# SCH___2023-02-11.net
KiCad netlist of a schematic drawn in EasyEDA
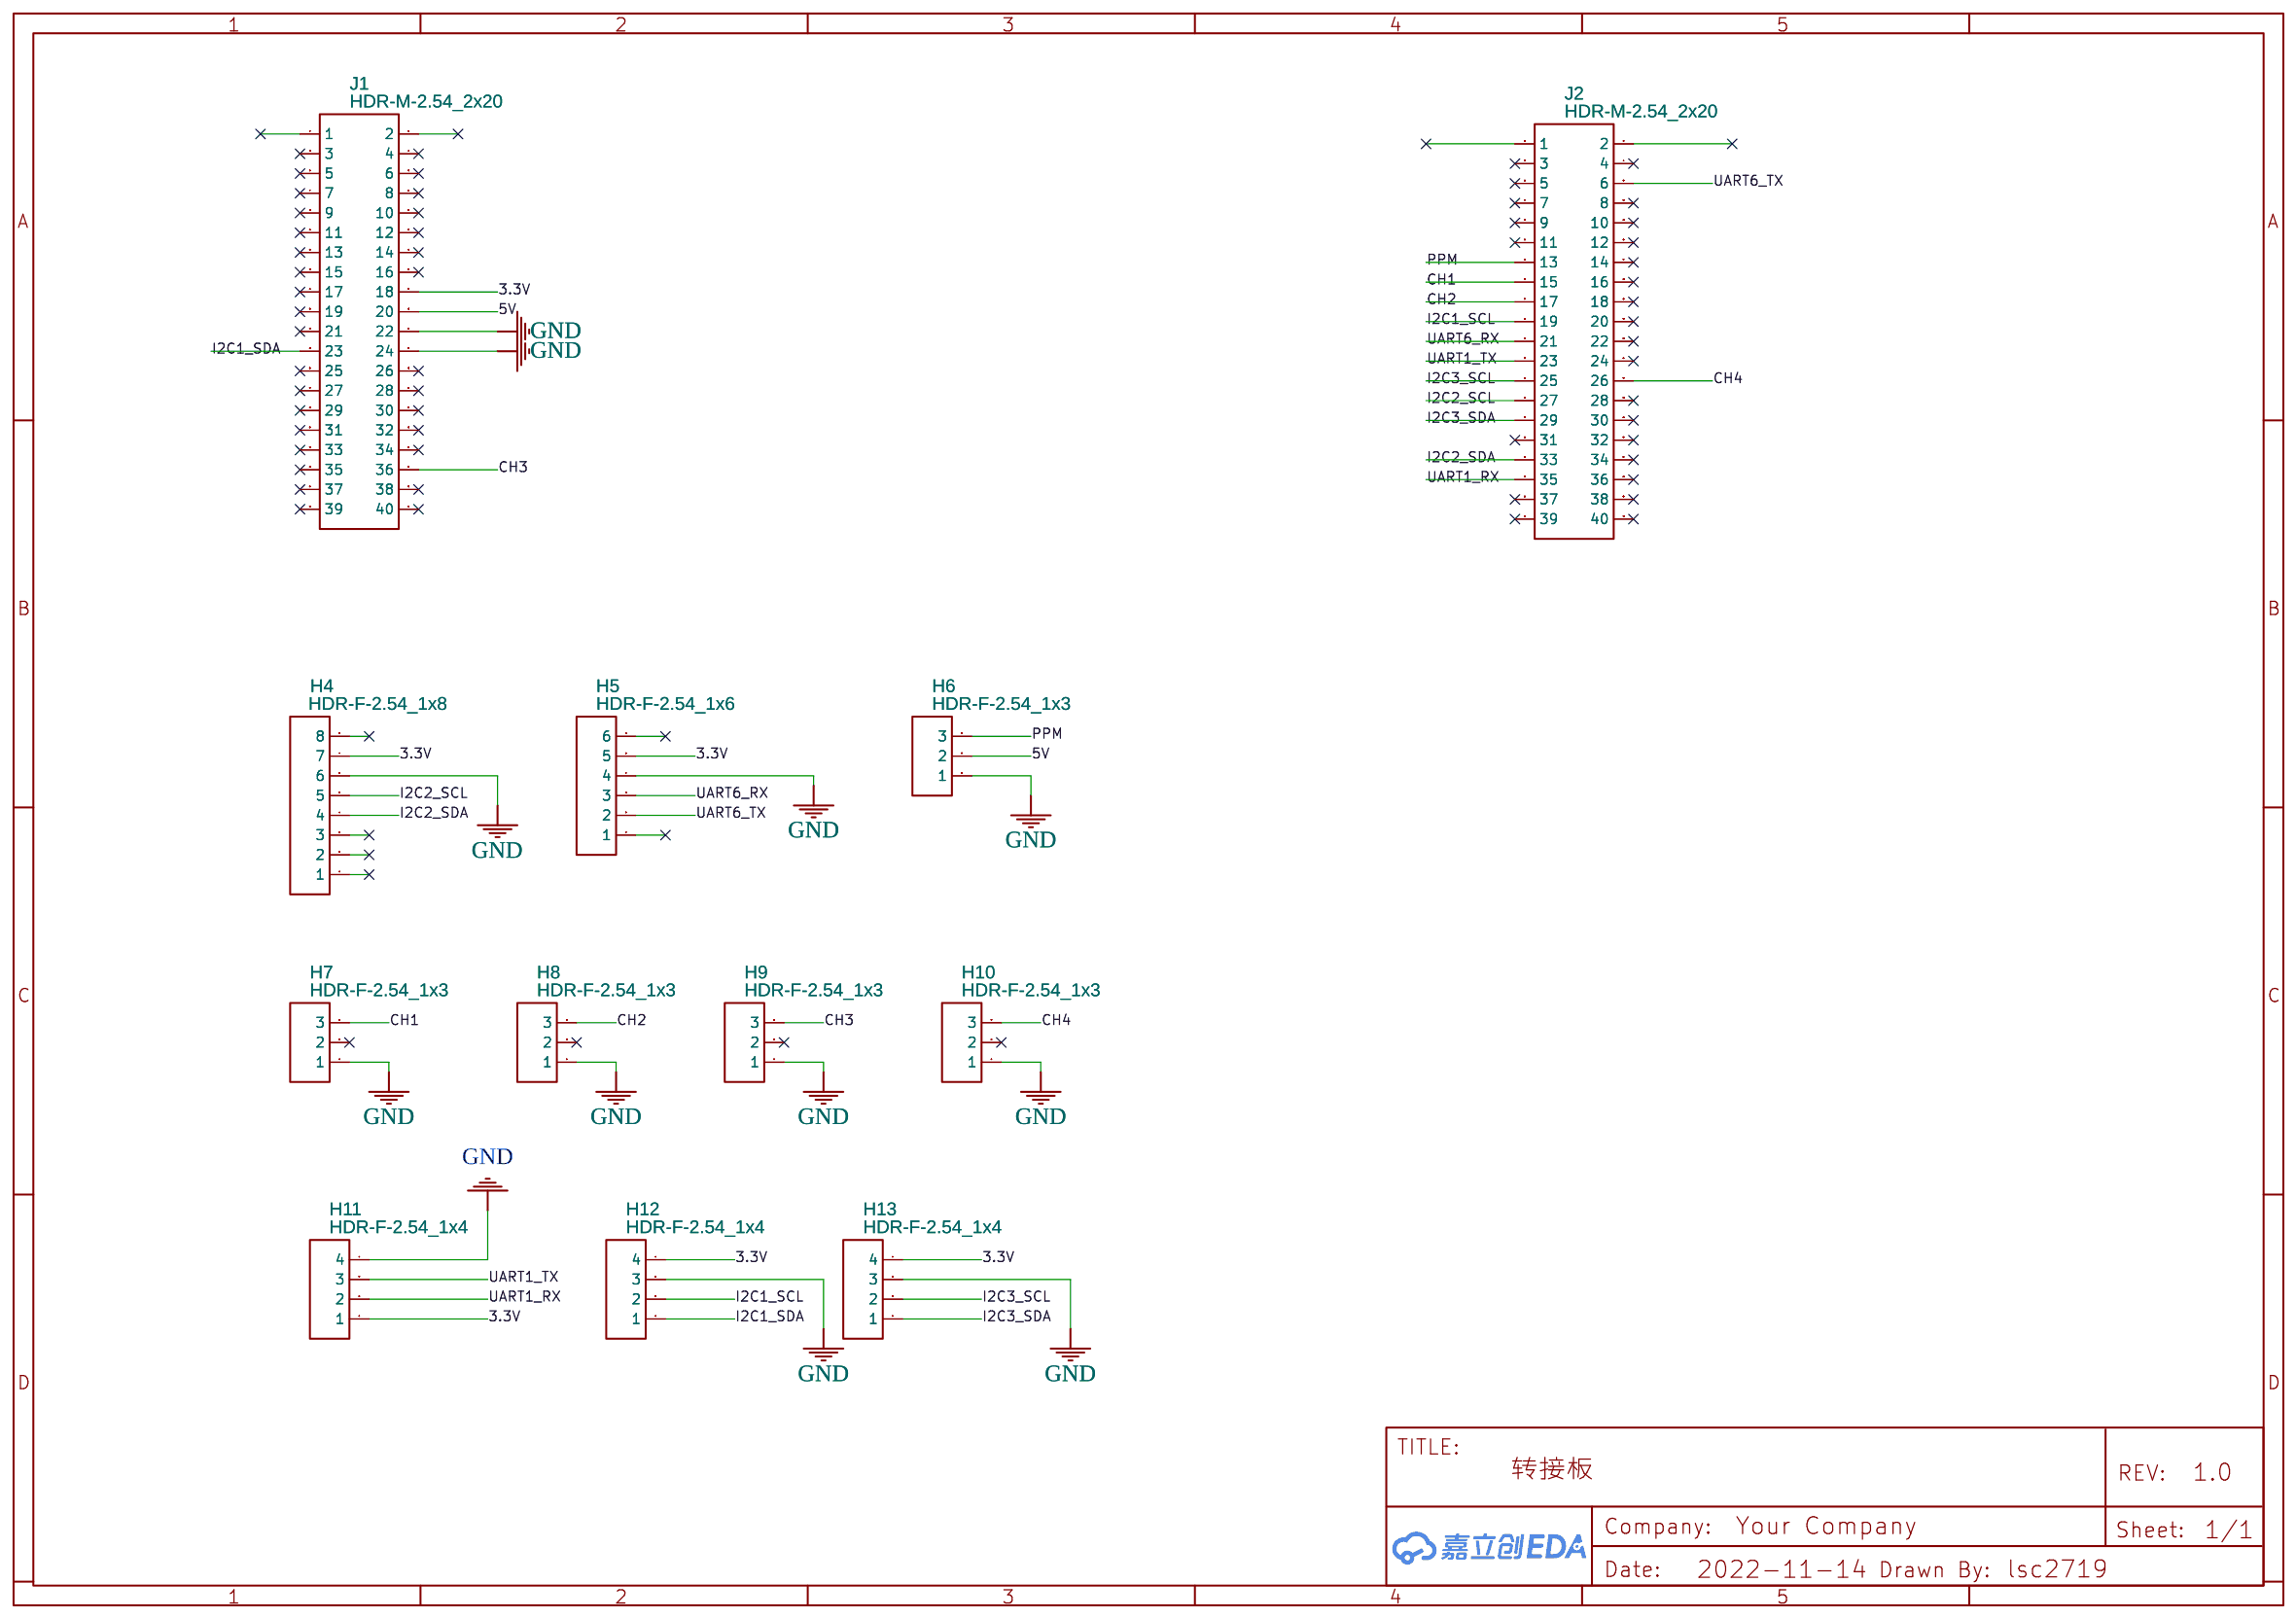
[diagram p0: schematic sheet]

(export (version "E")
  (design (tool "Eeschema 10.0.6"))
  (components
    (comp (ref "H4")
      (value "HDR-F-2.54_1x8")
      (fields (field (name "BOM_Supplier Part") "C225505"))
      (libsource (lib "") (part "HDR-F-2.54_1x8"))
    )
    (comp (ref "H5")
      (value "HDR-F-2.54_1x6")
      (fields (field (name "BOM_Supplier Part") "C40877"))
      (libsource (lib "") (part "HDR-F-2.54_1x6"))
    )
    (comp (ref "H6")
      (value "HDR-F-2.54_1x3")
      (fields (field (name "BOM_Supplier Part") "C146690"))
      (libsource (lib "") (part "HDR-F-2.54_1x3"))
    )
    (comp (ref "H7")
      (value "HDR-F-2.54_1x3")
      (fields (field (name "BOM_Supplier Part") "C146690"))
      (libsource (lib "") (part "HDR-F-2.54_1x3"))
    )
    (comp (ref "H8")
      (value "HDR-F-2.54_1x3")
      (fields (field (name "BOM_Supplier Part") "C146690"))
      (libsource (lib "") (part "HDR-F-2.54_1x3"))
    )
    (comp (ref "H9")
      (value "HDR-F-2.54_1x3")
      (fields (field (name "BOM_Supplier Part") "C146690"))
      (libsource (lib "") (part "HDR-F-2.54_1x3"))
    )
    (comp (ref "H10")
      (value "HDR-F-2.54_1x3")
      (fields (field (name "BOM_Supplier Part") "C146690"))
      (libsource (lib "") (part "HDR-F-2.54_1x3"))
    )
    (comp (ref "H11")
      (value "HDR-F-2.54_1x4")
      (fields (field (name "BOM_Supplier Part") "C225501"))
      (libsource (lib "") (part "HDR-F-2.54_1x4"))
    )
    (comp (ref "H12")
      (value "HDR-F-2.54_1x4")
      (fields (field (name "BOM_Supplier Part") "C225501"))
      (libsource (lib "") (part "HDR-F-2.54_1x4"))
    )
    (comp (ref "H13")
      (value "HDR-F-2.54_1x4")
      (fields (field (name "BOM_Supplier Part") "C225501"))
      (libsource (lib "") (part "HDR-F-2.54_1x4"))
    )
    (comp (ref "J1")
      (value "HDR-M-2.54_2x20")
      (fields (field (name "BOM_Supplier Part") "C50980"))
      (libsource (lib "") (part "HDR-M-2.54_2x20"))
    )
    (comp (ref "J2")
      (value "HDR-M-2.54_2x20")
      (fields (field (name "BOM_Supplier Part") "C50980"))
      (libsource (lib "") (part "HDR-M-2.54_2x20"))
    )
  )
  (nets
    (net (code "1") (name "/3.3V") (class "Default")
      (node (ref "H11") (pin "1") (pinfunction "1_1") (pintype "unspecified"))
      (node (ref "H12") (pin "4") (pinfunction "4_4") (pintype "unspecified"))
      (node (ref "H13") (pin "4") (pinfunction "4_4") (pintype "unspecified"))
      (node (ref "H4") (pin "7") (pinfunction "7_7") (pintype "unspecified"))
      (node (ref "H5") (pin "5") (pinfunction "5_5") (pintype "input"))
      (node (ref "J1") (pin "18") (pinfunction "18_18") (pintype "input"))
    )
    (net (code "2") (name "/5V") (class "Default")
      (node (ref "H6") (pin "2") (pinfunction "2_2") (pintype "input"))
      (node (ref "J1") (pin "20") (pinfunction "20_20") (pintype "input"))
    )
    (net (code "3") (name "/CH1") (class "Default")
      (node (ref "H7") (pin "3") (pinfunction "3_3") (pintype "input"))
      (node (ref "J2") (pin "15") (pinfunction "15_15") (pintype "input"))
    )
    (net (code "4") (name "/CH2") (class "Default")
      (node (ref "H8") (pin "3") (pinfunction "3_3") (pintype "input"))
      (node (ref "J2") (pin "17") (pinfunction "17_17") (pintype "input"))
    )
    (net (code "5") (name "/CH3") (class "Default")
      (node (ref "H9") (pin "3") (pinfunction "3_3") (pintype "input"))
      (node (ref "J1") (pin "36") (pinfunction "36_36") (pintype "input"))
    )
    (net (code "6") (name "/CH4") (class "Default")
      (node (ref "H10") (pin "3") (pinfunction "3_3") (pintype "input"))
      (node (ref "J2") (pin "26") (pinfunction "26_26") (pintype "input"))
    )
    (net (code "7") (name "/I2C1_SCL") (class "Default")
      (node (ref "H12") (pin "2") (pinfunction "2_2") (pintype "unspecified"))
      (node (ref "J2") (pin "19") (pinfunction "19_19") (pintype "input"))
    )
    (net (code "8") (name "/I2C1_SDA") (class "Default")
      (node (ref "H12") (pin "1") (pinfunction "1_1") (pintype "unspecified"))
      (node (ref "J1") (pin "23") (pinfunction "23_23") (pintype "input"))
    )
    (net (code "9") (name "/I2C2_SCL") (class "Default")
      (node (ref "H4") (pin "5") (pinfunction "5_5") (pintype "unspecified"))
      (node (ref "J2") (pin "27") (pinfunction "27_27") (pintype "input"))
    )
    (net (code "10") (name "/I2C2_SDA") (class "Default")
      (node (ref "H4") (pin "4") (pinfunction "4_4") (pintype "unspecified"))
      (node (ref "J2") (pin "33") (pinfunction "33_33") (pintype "input"))
    )
    (net (code "11") (name "/I2C3_SCL") (class "Default")
      (node (ref "H13") (pin "2") (pinfunction "2_2") (pintype "unspecified"))
      (node (ref "J2") (pin "25") (pinfunction "25_25") (pintype "input"))
    )
    (net (code "12") (name "/I2C3_SDA") (class "Default")
      (node (ref "H13") (pin "1") (pinfunction "1_1") (pintype "unspecified"))
      (node (ref "J2") (pin "29") (pinfunction "29_29") (pintype "input"))
    )
    (net (code "13") (name "/PPM") (class "Default")
      (node (ref "H6") (pin "3") (pinfunction "3_3") (pintype "input"))
      (node (ref "J2") (pin "13") (pinfunction "13_13") (pintype "input"))
    )
    (net (code "14") (name "/UART1_RX") (class "Default")
      (node (ref "H11") (pin "2") (pinfunction "2_2") (pintype "unspecified"))
      (node (ref "J2") (pin "35") (pinfunction "35_35") (pintype "input"))
    )
    (net (code "15") (name "/UART1_TX") (class "Default")
      (node (ref "H11") (pin "3") (pinfunction "3_3") (pintype "unspecified"))
      (node (ref "J2") (pin "23") (pinfunction "23_23") (pintype "input"))
    )
    (net (code "16") (name "/UART6_RX") (class "Default")
      (node (ref "H5") (pin "3") (pinfunction "3_3") (pintype "input"))
      (node (ref "J2") (pin "21") (pinfunction "21_21") (pintype "input"))
    )
    (net (code "17") (name "/UART6_TX") (class "Default")
      (node (ref "H5") (pin "2") (pinfunction "2_2") (pintype "input"))
      (node (ref "J2") (pin "6") (pinfunction "6_6") (pintype "input"))
    )
    (net (code "18") (name "GND") (class "Default")
      (node (ref "H10") (pin "1") (pinfunction "1_1") (pintype "input"))
      (node (ref "H11") (pin "4") (pinfunction "4_4") (pintype "unspecified"))
      (node (ref "H12") (pin "3") (pinfunction "3_3") (pintype "unspecified"))
      (node (ref "H13") (pin "3") (pinfunction "3_3") (pintype "unspecified"))
      (node (ref "H4") (pin "6") (pinfunction "6_6") (pintype "unspecified"))
      (node (ref "H5") (pin "4") (pinfunction "4_4") (pintype "input"))
      (node (ref "H6") (pin "1") (pinfunction "1_1") (pintype "input"))
      (node (ref "H7") (pin "1") (pinfunction "1_1") (pintype "input"))
      (node (ref "H8") (pin "1") (pinfunction "1_1") (pintype "input"))
      (node (ref "H9") (pin "1") (pinfunction "1_1") (pintype "input"))
      (node (ref "J1") (pin "22") (pinfunction "22_22") (pintype "input"))
      (node (ref "J1") (pin "24") (pinfunction "24_24") (pintype "input"))
    )
    (net (code "19") (name "unconnected-(H4-Pad1)") (class "Default")
      (node (ref "H4") (pin "1") (pinfunction "1_1") (pintype "unspecified+no_connect"))
    )
    (net (code "20") (name "unconnected-(H4-Pad2)") (class "Default")
      (node (ref "H4") (pin "2") (pinfunction "2_2") (pintype "unspecified+no_connect"))
    )
    (net (code "21") (name "unconnected-(H4-Pad3)") (class "Default")
      (node (ref "H4") (pin "3") (pinfunction "3_3") (pintype "unspecified+no_connect"))
    )
    (net (code "22") (name "unconnected-(H4-Pad8)") (class "Default")
      (node (ref "H4") (pin "8") (pinfunction "8_8") (pintype "unspecified+no_connect"))
    )
    (net (code "23") (name "unconnected-(H5-Pad1)") (class "Default")
      (node (ref "H5") (pin "1") (pinfunction "1_1") (pintype "input+no_connect"))
    )
    (net (code "24") (name "unconnected-(H5-Pad6)") (class "Default")
      (node (ref "H5") (pin "6") (pinfunction "6_6") (pintype "input+no_connect"))
    )
    (net (code "25") (name "unconnected-(H7-Pad2)") (class "Default")
      (node (ref "H7") (pin "2") (pinfunction "2_2") (pintype "input+no_connect"))
    )
    (net (code "26") (name "unconnected-(H8-Pad2)") (class "Default")
      (node (ref "H8") (pin "2") (pinfunction "2_2") (pintype "input+no_connect"))
    )
    (net (code "27") (name "unconnected-(H9-Pad2)") (class "Default")
      (node (ref "H9") (pin "2") (pinfunction "2_2") (pintype "input+no_connect"))
    )
    (net (code "28") (name "unconnected-(H10-Pad2)") (class "Default")
      (node (ref "H10") (pin "2") (pinfunction "2_2") (pintype "input+no_connect"))
    )
    (net (code "29") (name "unconnected-(J1-Pad1)") (class "Default")
      (node (ref "J1") (pin "1") (pinfunction "1_1") (pintype "input+no_connect"))
    )
    (net (code "30") (name "unconnected-(J1-Pad2)") (class "Default")
      (node (ref "J1") (pin "2") (pinfunction "2_2") (pintype "input+no_connect"))
    )
    (net (code "31") (name "unconnected-(J1-Pad3)") (class "Default")
      (node (ref "J1") (pin "3") (pinfunction "3_3") (pintype "input+no_connect"))
    )
    (net (code "32") (name "unconnected-(J1-Pad4)") (class "Default")
      (node (ref "J1") (pin "4") (pinfunction "4_4") (pintype "input+no_connect"))
    )
    (net (code "33") (name "unconnected-(J1-Pad5)") (class "Default")
      (node (ref "J1") (pin "5") (pinfunction "5_5") (pintype "input+no_connect"))
    )
    (net (code "34") (name "unconnected-(J1-Pad6)") (class "Default")
      (node (ref "J1") (pin "6") (pinfunction "6_6") (pintype "input+no_connect"))
    )
    (net (code "35") (name "unconnected-(J1-Pad7)") (class "Default")
      (node (ref "J1") (pin "7") (pinfunction "7_7") (pintype "input+no_connect"))
    )
    (net (code "36") (name "unconnected-(J1-Pad8)") (class "Default")
      (node (ref "J1") (pin "8") (pinfunction "8_8") (pintype "input+no_connect"))
    )
    (net (code "37") (name "unconnected-(J1-Pad9)") (class "Default")
      (node (ref "J1") (pin "9") (pinfunction "9_9") (pintype "input+no_connect"))
    )
    (net (code "38") (name "unconnected-(J1-Pad10)") (class "Default")
      (node (ref "J1") (pin "10") (pinfunction "10_10") (pintype "input+no_connect"))
    )
    (net (code "39") (name "unconnected-(J1-Pad11)") (class "Default")
      (node (ref "J1") (pin "11") (pinfunction "11_11") (pintype "input+no_connect"))
    )
    (net (code "40") (name "unconnected-(J1-Pad12)") (class "Default")
      (node (ref "J1") (pin "12") (pinfunction "12_12") (pintype "input+no_connect"))
    )
    (net (code "41") (name "unconnected-(J1-Pad13)") (class "Default")
      (node (ref "J1") (pin "13") (pinfunction "13_13") (pintype "input+no_connect"))
    )
    (net (code "42") (name "unconnected-(J1-Pad14)") (class "Default")
      (node (ref "J1") (pin "14") (pinfunction "14_14") (pintype "input+no_connect"))
    )
    (net (code "43") (name "unconnected-(J1-Pad15)") (class "Default")
      (node (ref "J1") (pin "15") (pinfunction "15_15") (pintype "input+no_connect"))
    )
    (net (code "44") (name "unconnected-(J1-Pad16)") (class "Default")
      (node (ref "J1") (pin "16") (pinfunction "16_16") (pintype "input+no_connect"))
    )
    (net (code "45") (name "unconnected-(J1-Pad17)") (class "Default")
      (node (ref "J1") (pin "17") (pinfunction "17_17") (pintype "input+no_connect"))
    )
    (net (code "46") (name "unconnected-(J1-Pad19)") (class "Default")
      (node (ref "J1") (pin "19") (pinfunction "19_19") (pintype "input+no_connect"))
    )
    (net (code "47") (name "unconnected-(J1-Pad21)") (class "Default")
      (node (ref "J1") (pin "21") (pinfunction "21_21") (pintype "input+no_connect"))
    )
    (net (code "48") (name "unconnected-(J1-Pad25)") (class "Default")
      (node (ref "J1") (pin "25") (pinfunction "25_25") (pintype "input+no_connect"))
    )
    (net (code "49") (name "unconnected-(J1-Pad26)") (class "Default")
      (node (ref "J1") (pin "26") (pinfunction "26_26") (pintype "input+no_connect"))
    )
    (net (code "50") (name "unconnected-(J1-Pad27)") (class "Default")
      (node (ref "J1") (pin "27") (pinfunction "27_27") (pintype "input+no_connect"))
    )
    (net (code "51") (name "unconnected-(J1-Pad28)") (class "Default")
      (node (ref "J1") (pin "28") (pinfunction "28_28") (pintype "input+no_connect"))
    )
    (net (code "52") (name "unconnected-(J1-Pad29)") (class "Default")
      (node (ref "J1") (pin "29") (pinfunction "29_29") (pintype "input+no_connect"))
    )
    (net (code "53") (name "unconnected-(J1-Pad30)") (class "Default")
      (node (ref "J1") (pin "30") (pinfunction "30_30") (pintype "input+no_connect"))
    )
    (net (code "54") (name "unconnected-(J1-Pad31)") (class "Default")
      (node (ref "J1") (pin "31") (pinfunction "31_31") (pintype "input+no_connect"))
    )
    (net (code "55") (name "unconnected-(J1-Pad32)") (class "Default")
      (node (ref "J1") (pin "32") (pinfunction "32_32") (pintype "input+no_connect"))
    )
    (net (code "56") (name "unconnected-(J1-Pad33)") (class "Default")
      (node (ref "J1") (pin "33") (pinfunction "33_33") (pintype "input+no_connect"))
    )
    (net (code "57") (name "unconnected-(J1-Pad34)") (class "Default")
      (node (ref "J1") (pin "34") (pinfunction "34_34") (pintype "input+no_connect"))
    )
    (net (code "58") (name "unconnected-(J1-Pad35)") (class "Default")
      (node (ref "J1") (pin "35") (pinfunction "35_35") (pintype "input+no_connect"))
    )
    (net (code "59") (name "unconnected-(J1-Pad37)") (class "Default")
      (node (ref "J1") (pin "37") (pinfunction "37_37") (pintype "input+no_connect"))
    )
    (net (code "60") (name "unconnected-(J1-Pad38)") (class "Default")
      (node (ref "J1") (pin "38") (pinfunction "38_38") (pintype "input+no_connect"))
    )
    (net (code "61") (name "unconnected-(J1-Pad39)") (class "Default")
      (node (ref "J1") (pin "39") (pinfunction "39_39") (pintype "input+no_connect"))
    )
    (net (code "62") (name "unconnected-(J1-Pad40)") (class "Default")
      (node (ref "J1") (pin "40") (pinfunction "40_40") (pintype "input+no_connect"))
    )
    (net (code "63") (name "unconnected-(J2-Pad1)") (class "Default")
      (node (ref "J2") (pin "1") (pinfunction "1_1") (pintype "input+no_connect"))
    )
    (net (code "64") (name "unconnected-(J2-Pad2)") (class "Default")
      (node (ref "J2") (pin "2") (pinfunction "2_2") (pintype "input+no_connect"))
    )
    (net (code "65") (name "unconnected-(J2-Pad3)") (class "Default")
      (node (ref "J2") (pin "3") (pinfunction "3_3") (pintype "input+no_connect"))
    )
    (net (code "66") (name "unconnected-(J2-Pad4)") (class "Default")
      (node (ref "J2") (pin "4") (pinfunction "4_4") (pintype "input+no_connect"))
    )
    (net (code "67") (name "unconnected-(J2-Pad5)") (class "Default")
      (node (ref "J2") (pin "5") (pinfunction "5_5") (pintype "input+no_connect"))
    )
    (net (code "68") (name "unconnected-(J2-Pad7)") (class "Default")
      (node (ref "J2") (pin "7") (pinfunction "7_7") (pintype "input+no_connect"))
    )
    (net (code "69") (name "unconnected-(J2-Pad8)") (class "Default")
      (node (ref "J2") (pin "8") (pinfunction "8_8") (pintype "input+no_connect"))
    )
    (net (code "70") (name "unconnected-(J2-Pad9)") (class "Default")
      (node (ref "J2") (pin "9") (pinfunction "9_9") (pintype "input+no_connect"))
    )
    (net (code "71") (name "unconnected-(J2-Pad10)") (class "Default")
      (node (ref "J2") (pin "10") (pinfunction "10_10") (pintype "input+no_connect"))
    )
    (net (code "72") (name "unconnected-(J2-Pad11)") (class "Default")
      (node (ref "J2") (pin "11") (pinfunction "11_11") (pintype "input+no_connect"))
    )
    (net (code "73") (name "unconnected-(J2-Pad12)") (class "Default")
      (node (ref "J2") (pin "12") (pinfunction "12_12") (pintype "input+no_connect"))
    )
    (net (code "74") (name "unconnected-(J2-Pad14)") (class "Default")
      (node (ref "J2") (pin "14") (pinfunction "14_14") (pintype "input+no_connect"))
    )
    (net (code "75") (name "unconnected-(J2-Pad16)") (class "Default")
      (node (ref "J2") (pin "16") (pinfunction "16_16") (pintype "input+no_connect"))
    )
    (net (code "76") (name "unconnected-(J2-Pad18)") (class "Default")
      (node (ref "J2") (pin "18") (pinfunction "18_18") (pintype "input+no_connect"))
    )
    (net (code "77") (name "unconnected-(J2-Pad20)") (class "Default")
      (node (ref "J2") (pin "20") (pinfunction "20_20") (pintype "input+no_connect"))
    )
    (net (code "78") (name "unconnected-(J2-Pad22)") (class "Default")
      (node (ref "J2") (pin "22") (pinfunction "22_22") (pintype "input+no_connect"))
    )
    (net (code "79") (name "unconnected-(J2-Pad24)") (class "Default")
      (node (ref "J2") (pin "24") (pinfunction "24_24") (pintype "input+no_connect"))
    )
    (net (code "80") (name "unconnected-(J2-Pad28)") (class "Default")
      (node (ref "J2") (pin "28") (pinfunction "28_28") (pintype "input+no_connect"))
    )
    (net (code "81") (name "unconnected-(J2-Pad30)") (class "Default")
      (node (ref "J2") (pin "30") (pinfunction "30_30") (pintype "input+no_connect"))
    )
    (net (code "82") (name "unconnected-(J2-Pad31)") (class "Default")
      (node (ref "J2") (pin "31") (pinfunction "31_31") (pintype "input+no_connect"))
    )
    (net (code "83") (name "unconnected-(J2-Pad32)") (class "Default")
      (node (ref "J2") (pin "32") (pinfunction "32_32") (pintype "input+no_connect"))
    )
    (net (code "84") (name "unconnected-(J2-Pad34)") (class "Default")
      (node (ref "J2") (pin "34") (pinfunction "34_34") (pintype "input+no_connect"))
    )
    (net (code "85") (name "unconnected-(J2-Pad36)") (class "Default")
      (node (ref "J2") (pin "36") (pinfunction "36_36") (pintype "input+no_connect"))
    )
    (net (code "86") (name "unconnected-(J2-Pad37)") (class "Default")
      (node (ref "J2") (pin "37") (pinfunction "37_37") (pintype "input+no_connect"))
    )
    (net (code "87") (name "unconnected-(J2-Pad38)") (class "Default")
      (node (ref "J2") (pin "38") (pinfunction "38_38") (pintype "input+no_connect"))
    )
    (net (code "88") (name "unconnected-(J2-Pad39)") (class "Default")
      (node (ref "J2") (pin "39") (pinfunction "39_39") (pintype "input+no_connect"))
    )
    (net (code "89") (name "unconnected-(J2-Pad40)") (class "Default")
      (node (ref "J2") (pin "40") (pinfunction "40_40") (pintype "input+no_connect"))
    )
  )
)
